# DashHub.net
KiCad netlist of a schematic drawn in EAGLE
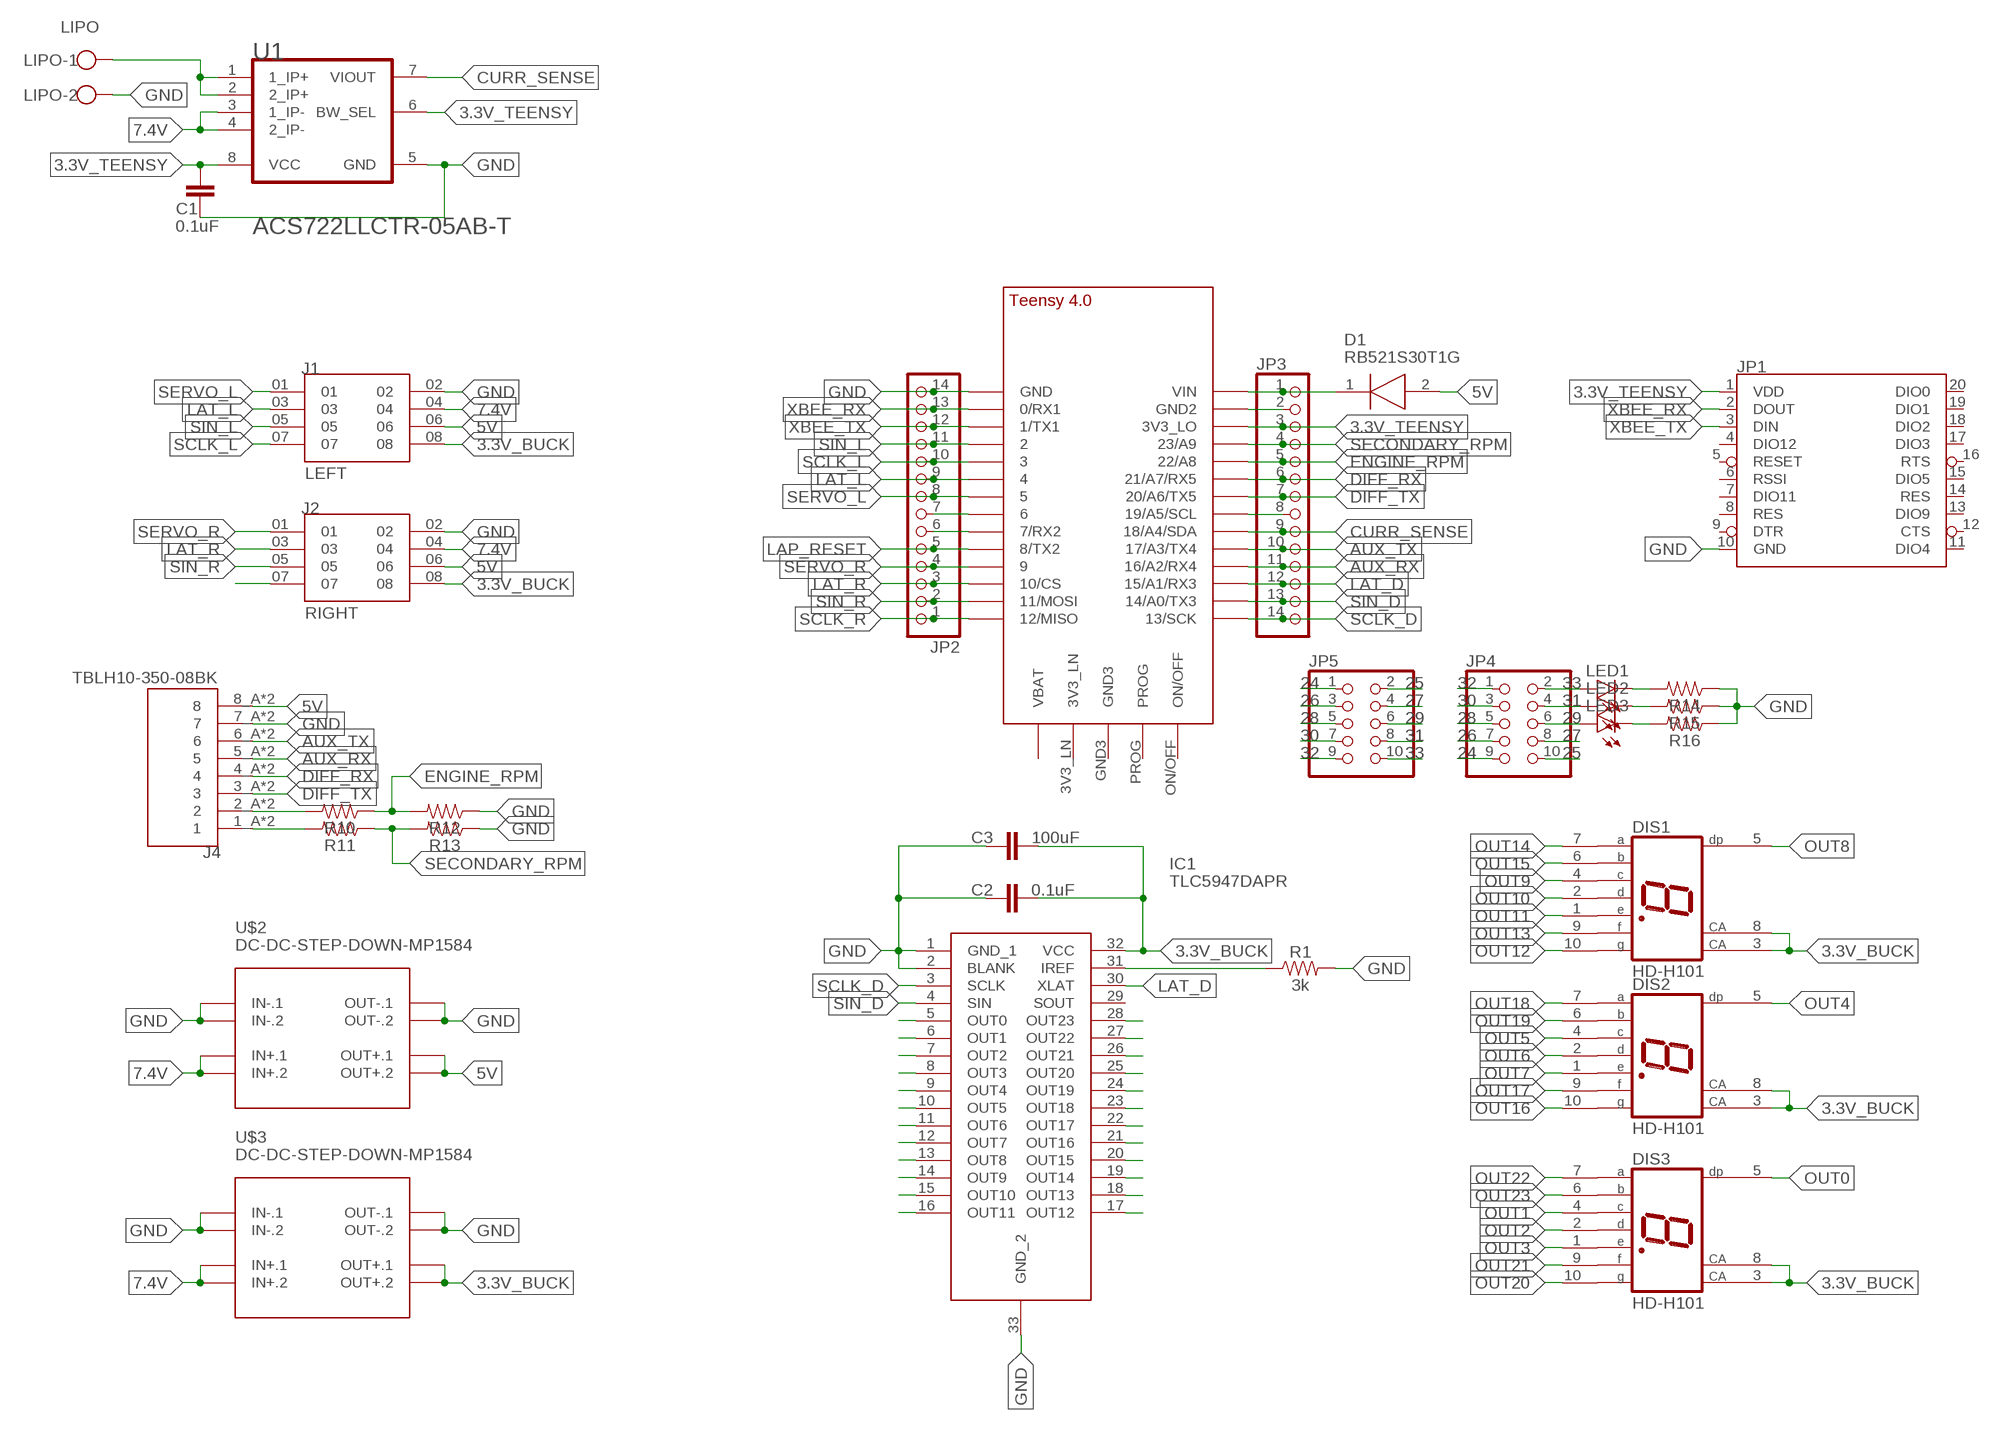
[diagram p0: schematic, sheet 1]

(export (version "E")
  (design (tool "Eeschema 10.0.6"))
  (components
    (comp (ref "C1")
      (value "0.1uF")
      (footprint "eagle-import:C0402")
      (libsource (lib "eagle-import") (part "C-EUC0402"))
    )
    (comp (ref "C2")
      (value "0.1uF")
      (footprint "eagle-import:C0402")
      (libsource (lib "eagle-import") (part "C-EUC0402"))
    )
    (comp (ref "C3")
      (value "100uF")
      (footprint "eagle-import:C1206")
      (libsource (lib "eagle-import") (part "C-EUC1206"))
    )
    (comp (ref "D1")
      (value "RB521S30T1G")
      (footprint "eagle-import:SODFL1608X70N")
      (fields (field (name "MOUSER_PART_NUMBER") "863-RB521S30T1G"))
      (libsource (lib "eagle-import") (part "RB521S30T1G"))
    )
    (comp (ref "DIS1")
      (value "HD-H101")
      (footprint "eagle-import:HDSP-M")
      (libsource (lib "eagle-import") (part "HD-H101"))
    )
    (comp (ref "DIS2")
      (value "HD-H101")
      (footprint "eagle-import:HDSP-M")
      (libsource (lib "eagle-import") (part "HD-H101"))
    )
    (comp (ref "DIS3")
      (value "HD-H101")
      (footprint "eagle-import:HDSP-M")
      (libsource (lib "eagle-import") (part "HD-H101"))
    )
    (comp (ref "IC1")
      (value "TLC5947DAPR")
      (footprint "eagle-import:SOP65P810X120-33N")
      (fields (field (name "MOUSER_PART_NUMBER") "595-TLC5947DAPR"))
      (libsource (lib "eagle-import") (part "TLC5947DAPR"))
    )
    (comp (ref "J1")
      (value "LEFT")
      (footprint "eagle-import:SAMTEC_ESW-104-23-L-D")
      (fields (field (name "MANUFACTURER") "Samtec Inc."))
      (libsource (lib "eagle-import") (part "ESW-104-23-L-D"))
    )
    (comp (ref "J2")
      (value "RIGHT")
      (footprint "eagle-import:SAMTEC_ESW-104-23-L-D")
      (fields (field (name "MANUFACTURER") "Samtec Inc."))
      (libsource (lib "eagle-import") (part "ESW-104-23-L-D"))
    )
    (comp (ref "J4")
      (value "TBLH10-350-08BK")
      (footprint "eagle-import:CUI_TBLH10-350-08BK")
      (fields (field (name "MANUFACTURER") "CUI"))
      (libsource (lib "eagle-import") (part "TBLH10-350-08BK"))
    )
    (comp (ref "JP1")
      (value "XBEE")
      (footprint "eagle-import:XBEE")
      (libsource (lib "eagle-import") (part "XBEE"))
    )
    (comp (ref "JP2")
      (value "PINHD-1X14")
      (footprint "eagle-import:1X14")
      (libsource (lib "eagle-import") (part "PINHD-1X14"))
    )
    (comp (ref "JP3")
      (value "PINHD-1X14")
      (footprint "eagle-import:1X14")
      (libsource (lib "eagle-import") (part "PINHD-1X14"))
    )
    (comp (ref "JP4")
      (value "PINHD-2X5")
      (footprint "eagle-import:2X05")
      (libsource (lib "eagle-import") (part "PINHD-2X5"))
    )
    (comp (ref "JP5")
      (value "PINHD-2X5")
      (footprint "eagle-import:2X05")
      (libsource (lib "eagle-import") (part "PINHD-2X5"))
    )
    (comp (ref "LED1")
      (value "LEDCHIPLED_1206")
      (footprint "eagle-import:CHIPLED_1206")
      (libsource (lib "eagle-import") (part "LEDCHIPLED_1206"))
    )
    (comp (ref "LED2")
      (value "LEDCHIPLED_1206")
      (footprint "eagle-import:CHIPLED_1206")
      (libsource (lib "eagle-import") (part "LEDCHIPLED_1206"))
    )
    (comp (ref "LED3")
      (value "LEDCHIPLED_1206")
      (footprint "eagle-import:CHIPLED_1206")
      (libsource (lib "eagle-import") (part "LEDCHIPLED_1206"))
    )
    (comp (ref "LIPO")
      (value "LIPO")
      (footprint "eagle-import:W237-102")
      (fields (field (name "MPN") "237-102"))
      (libsource (lib "eagle-import") (part "W237-102"))
    )
    (comp (ref "R1")
      (value "3k")
      (footprint "eagle-import:AXIAL-0.3")
      (libsource (lib "eagle-import") (part "RESISTORAXIAL-0.3"))
    )
    (comp (ref "R10")
      (value "RESISTORAXIAL-0.3")
      (footprint "eagle-import:AXIAL-0.3")
      (libsource (lib "eagle-import") (part "RESISTORAXIAL-0.3"))
    )
    (comp (ref "R11")
      (value "RESISTORAXIAL-0.3")
      (footprint "eagle-import:AXIAL-0.3")
      (libsource (lib "eagle-import") (part "RESISTORAXIAL-0.3"))
    )
    (comp (ref "R12")
      (value "RESISTORAXIAL-0.3")
      (footprint "eagle-import:AXIAL-0.3")
      (libsource (lib "eagle-import") (part "RESISTORAXIAL-0.3"))
    )
    (comp (ref "R13")
      (value "RESISTORAXIAL-0.3")
      (footprint "eagle-import:AXIAL-0.3")
      (libsource (lib "eagle-import") (part "RESISTORAXIAL-0.3"))
    )
    (comp (ref "R14")
      (value "RESISTORAXIAL-0.3")
      (footprint "eagle-import:AXIAL-0.3")
      (libsource (lib "eagle-import") (part "RESISTORAXIAL-0.3"))
    )
    (comp (ref "R15")
      (value "RESISTORAXIAL-0.3")
      (footprint "eagle-import:AXIAL-0.3")
      (libsource (lib "eagle-import") (part "RESISTORAXIAL-0.3"))
    )
    (comp (ref "R16")
      (value "RESISTORAXIAL-0.3")
      (footprint "eagle-import:AXIAL-0.3")
      (libsource (lib "eagle-import") (part "RESISTORAXIAL-0.3"))
    )
    (comp (ref "U$1")
      (value "TEENSY_4.0-BASIC")
      (footprint "eagle-import:TEENSY_4.0-BASIC")
      (libsource (lib "eagle-import") (part "TEENSY_4.0-BASIC"))
    )
    (comp (ref "U$2")
      (value "DC-DC-STEP-DOWN-MP1584")
      (footprint "eagle-import:DC-DC-STEP-DOWN-MP1584")
      (libsource (lib "eagle-import") (part "DC-DC-STEP-DOWN-MP1584"))
    )
    (comp (ref "U$3")
      (value "DC-DC-STEP-DOWN-MP1584")
      (footprint "eagle-import:DC-DC-STEP-DOWN-MP1584")
      (libsource (lib "eagle-import") (part "DC-DC-STEP-DOWN-MP1584"))
    )
    (comp (ref "U1")
      (value "ALLEGRO_MICROSYSTEMS_ACS722LLCTR-05AB-TALLEGRO_MICROSYSTEMS_ACS722LLCTR-05AB-T_0_0")
      (footprint "eagle-import:ALLEGRO_MICROSYSTEMS_ACS722LLCTR-05AB-T_0")
      (fields (field (name "MF") "Allegro MicroSystems") (field (name "MPN") "ACS722LLCTR-05AB-T"))
      (libsource (lib "eagle-import") (part "ALLEGRO_MICROSYSTEMS_ACS722LLCTR-05AB-TALLEGRO_MICROSYSTEMS_ACS722LLCTR-05AB-T_0_0"))
    )
  )
  (nets
    (net (code "1") (name "/24") (class "Default")
      (node (ref "JP4") (pin "9") (pinfunction "9_9") (pintype "passive"))
      (node (ref "JP5") (pin "1") (pinfunction "1_1") (pintype "passive"))
    )
    (net (code "2") (name "/25") (class "Default")
      (node (ref "JP4") (pin "10") (pinfunction "10_10") (pintype "passive"))
      (node (ref "JP5") (pin "2") (pinfunction "2_2") (pintype "passive"))
    )
    (net (code "3") (name "/26") (class "Default")
      (node (ref "JP4") (pin "7") (pinfunction "7_7") (pintype "passive"))
      (node (ref "JP5") (pin "3") (pinfunction "3_3") (pintype "passive"))
    )
    (net (code "4") (name "/27") (class "Default")
      (node (ref "JP4") (pin "8") (pinfunction "8_8") (pintype "passive"))
      (node (ref "JP5") (pin "4") (pinfunction "4_4") (pintype "passive"))
    )
    (net (code "5") (name "/28") (class "Default")
      (node (ref "JP4") (pin "5") (pinfunction "5_5") (pintype "passive"))
      (node (ref "JP5") (pin "5") (pinfunction "5_5") (pintype "passive"))
    )
    (net (code "6") (name "/29") (class "Default")
      (node (ref "JP4") (pin "6") (pinfunction "6_6") (pintype "passive"))
      (node (ref "JP5") (pin "6") (pinfunction "6_6") (pintype "passive"))
      (node (ref "LED3") (pin "A") (pinfunction "A_A") (pintype "passive"))
    )
    (net (code "7") (name "/30") (class "Default")
      (node (ref "JP4") (pin "3") (pinfunction "3_3") (pintype "passive"))
      (node (ref "JP5") (pin "7") (pinfunction "7_7") (pintype "passive"))
    )
    (net (code "8") (name "/31") (class "Default")
      (node (ref "JP4") (pin "4") (pinfunction "4_4") (pintype "passive"))
      (node (ref "JP5") (pin "8") (pinfunction "8_8") (pintype "passive"))
      (node (ref "LED2") (pin "A") (pinfunction "A_A") (pintype "passive"))
    )
    (net (code "9") (name "/32") (class "Default")
      (node (ref "JP4") (pin "1") (pinfunction "1_1") (pintype "passive"))
      (node (ref "JP5") (pin "9") (pinfunction "9_9") (pintype "passive"))
    )
    (net (code "10") (name "/33") (class "Default")
      (node (ref "JP4") (pin "2") (pinfunction "2_2") (pintype "passive"))
      (node (ref "JP5") (pin "10") (pinfunction "10_10") (pintype "passive"))
      (node (ref "LED1") (pin "A") (pinfunction "A_A") (pintype "passive"))
    )
    (net (code "11") (name "3.3V_BUCK") (class "Default")
      (node (ref "C2") (pin "2") (pinfunction "2_2") (pintype "passive"))
      (node (ref "C3") (pin "2") (pinfunction "2_2") (pintype "passive"))
      (node (ref "DIS1") (pin "3") (pinfunction "CA_3") (pintype "passive"))
      (node (ref "DIS1") (pin "8") (pinfunction "CA_8") (pintype "passive"))
      (node (ref "DIS2") (pin "3") (pinfunction "CA_3") (pintype "passive"))
      (node (ref "DIS2") (pin "8") (pinfunction "CA_8") (pintype "passive"))
      (node (ref "DIS3") (pin "3") (pinfunction "CA_3") (pintype "passive"))
      (node (ref "DIS3") (pin "8") (pinfunction "CA_8") (pintype "passive"))
      (node (ref "IC1") (pin "32") (pinfunction "VCC_32") (pintype "power_in"))
      (node (ref "J1") (pin "08") (pinfunction "08_08") (pintype "passive"))
      (node (ref "J2") (pin "08") (pinfunction "08_08") (pintype "passive"))
      (node (ref "U$3") (pin "OUT+.1") (pinfunction "OUT+.1_OUT+.1") (pintype "bidirectional"))
      (node (ref "U$3") (pin "OUT+.2") (pinfunction "OUT+.2_OUT+.2") (pintype "bidirectional"))
    )
    (net (code "12") (name "3.3V_TEENSY") (class "Default")
      (node (ref "C1") (pin "2") (pinfunction "2_2") (pintype "passive"))
      (node (ref "JP1") (pin "1") (pinfunction "VDD_1") (pintype "power_in"))
      (node (ref "JP3") (pin "3") (pinfunction "3_3") (pintype "passive"))
      (node (ref "U$1") (pin "3V3_LO") (pinfunction "3V3_LO_3V3_LO") (pintype "bidirectional"))
      (node (ref "U1") (pin "6") (pinfunction "BW_SEL_6") (pintype "input"))
      (node (ref "U1") (pin "8") (pinfunction "VCC_8") (pintype "power_in"))
    )
    (net (code "13") (name "5V") (class "Default")
      (node (ref "D1") (pin "2") (pinfunction "A_2") (pintype "bidirectional"))
      (node (ref "J1") (pin "06") (pinfunction "06_06") (pintype "passive"))
      (node (ref "J2") (pin "06") (pinfunction "06_06") (pintype "passive"))
      (node (ref "J4") (pin "8_A") (pinfunction "8_8_A") (pintype "passive"))
      (node (ref "J4") (pin "8_B") (pinfunction "8_8_B") (pintype "passive"))
      (node (ref "U$2") (pin "OUT+.1") (pinfunction "OUT+.1_OUT+.1") (pintype "bidirectional"))
      (node (ref "U$2") (pin "OUT+.2") (pinfunction "OUT+.2_OUT+.2") (pintype "bidirectional"))
    )
    (net (code "14") (name "7.4V") (class "Default")
      (node (ref "J1") (pin "04") (pinfunction "04_04") (pintype "passive"))
      (node (ref "J2") (pin "04") (pinfunction "04_04") (pintype "passive"))
      (node (ref "U$2") (pin "IN+.1") (pinfunction "IN+.1_IN+.1") (pintype "bidirectional"))
      (node (ref "U$2") (pin "IN+.2") (pinfunction "IN+.2_IN+.2") (pintype "bidirectional"))
      (node (ref "U$3") (pin "IN+.1") (pinfunction "IN+.1_IN+.1") (pintype "bidirectional"))
      (node (ref "U$3") (pin "IN+.2") (pinfunction "IN+.2_IN+.2") (pintype "bidirectional"))
      (node (ref "U1") (pin "3") (pinfunction "1_IP-_3") (pintype "input"))
      (node (ref "U1") (pin "4") (pinfunction "2_IP-_4") (pintype "input"))
    )
    (net (code "15") (name "AUX_RX") (class "Default")
      (node (ref "J4") (pin "5_A") (pinfunction "5_5_A") (pintype "passive"))
      (node (ref "J4") (pin "5_B") (pinfunction "5_5_B") (pintype "passive"))
      (node (ref "JP3") (pin "11") (pinfunction "11_11") (pintype "passive"))
      (node (ref "U$1") (pin "16/A2") (pinfunction "16/A2/RX4_16/A2") (pintype "bidirectional"))
    )
    (net (code "16") (name "AUX_TX") (class "Default")
      (node (ref "J4") (pin "6_A") (pinfunction "6_6_A") (pintype "passive"))
      (node (ref "J4") (pin "6_B") (pinfunction "6_6_B") (pintype "passive"))
      (node (ref "JP3") (pin "10") (pinfunction "10_10") (pintype "passive"))
      (node (ref "U$1") (pin "17/A3") (pinfunction "17/A3/TX4_17/A3") (pintype "bidirectional"))
    )
    (net (code "17") (name "CURR_SENSE") (class "Default")
      (node (ref "JP3") (pin "9") (pinfunction "9_9") (pintype "passive"))
      (node (ref "U$1") (pin "18/A4/SDA") (pinfunction "18/A4/SDA_18/A4/SDA") (pintype "bidirectional"))
      (node (ref "U1") (pin "7") (pinfunction "VIOUT_7") (pintype "output"))
    )
    (net (code "18") (name "DIFF_RX") (class "Default")
      (node (ref "J4") (pin "4_A") (pinfunction "4_4_A") (pintype "passive"))
      (node (ref "J4") (pin "4_B") (pinfunction "4_4_B") (pintype "passive"))
      (node (ref "JP3") (pin "6") (pinfunction "6_6") (pintype "passive"))
      (node (ref "U$1") (pin "21/A7") (pinfunction "21/A7/RX5_21/A7") (pintype "bidirectional"))
    )
    (net (code "19") (name "DIFF_TX") (class "Default")
      (node (ref "J4") (pin "3_A") (pinfunction "3_3_A") (pintype "passive"))
      (node (ref "J4") (pin "3_B") (pinfunction "3_3_B") (pintype "passive"))
      (node (ref "JP3") (pin "7") (pinfunction "7_7") (pintype "passive"))
      (node (ref "U$1") (pin "20/A6") (pinfunction "20/A6/TX5_20/A6") (pintype "bidirectional"))
    )
    (net (code "20") (name "ENGINE_RPM") (class "Default")
      (node (ref "JP3") (pin "5") (pinfunction "5_5") (pintype "passive"))
      (node (ref "R10") (pin "P$1") (pinfunction "1_P$1") (pintype "passive"))
      (node (ref "R12") (pin "P$2") (pinfunction "2_P$2") (pintype "passive"))
      (node (ref "U$1") (pin "22/A8") (pinfunction "22/A8_22/A8") (pintype "bidirectional"))
    )
    (net (code "21") (name "GND") (class "Default")
      (node (ref "C1") (pin "1") (pinfunction "1_1") (pintype "passive"))
      (node (ref "C2") (pin "1") (pinfunction "1_1") (pintype "passive"))
      (node (ref "C3") (pin "1") (pinfunction "1_1") (pintype "passive"))
      (node (ref "IC1") (pin "1") (pinfunction "GND_1_1") (pintype "power_in"))
      (node (ref "IC1") (pin "2") (pinfunction "BLANK_2") (pintype "input"))
      (node (ref "IC1") (pin "33") (pinfunction "GND_2_33") (pintype "power_in"))
      (node (ref "J1") (pin "02") (pinfunction "02_02") (pintype "passive"))
      (node (ref "J2") (pin "02") (pinfunction "02_02") (pintype "passive"))
      (node (ref "J4") (pin "7_A") (pinfunction "7_7_A") (pintype "passive"))
      (node (ref "J4") (pin "7_B") (pinfunction "7_7_B") (pintype "passive"))
      (node (ref "JP1") (pin "10") (pinfunction "GND_10") (pintype "power_in"))
      (node (ref "JP2") (pin "14") (pinfunction "14_14") (pintype "passive"))
      (node (ref "LIPO") (pin "2") (pinfunction "KL_2") (pintype "passive"))
      (node (ref "R1") (pin "P$2") (pinfunction "2_P$2") (pintype "passive"))
      (node (ref "R12") (pin "P$1") (pinfunction "1_P$1") (pintype "passive"))
      (node (ref "R13") (pin "P$1") (pinfunction "1_P$1") (pintype "passive"))
      (node (ref "R14") (pin "P$1") (pinfunction "1_P$1") (pintype "passive"))
      (node (ref "R15") (pin "P$1") (pinfunction "1_P$1") (pintype "passive"))
      (node (ref "R16") (pin "P$1") (pinfunction "1_P$1") (pintype "passive"))
      (node (ref "U$1") (pin "GND") (pinfunction "GND_GND") (pintype "bidirectional"))
      (node (ref "U$2") (pin "IN-.1") (pinfunction "IN-.1_IN-.1") (pintype "bidirectional"))
      (node (ref "U$2") (pin "IN-.2") (pinfunction "IN-.2_IN-.2") (pintype "bidirectional"))
      (node (ref "U$2") (pin "OUT-.1") (pinfunction "OUT-.1_OUT-.1") (pintype "bidirectional"))
      (node (ref "U$2") (pin "OUT-.2") (pinfunction "OUT-.2_OUT-.2") (pintype "bidirectional"))
      (node (ref "U$3") (pin "IN-.1") (pinfunction "IN-.1_IN-.1") (pintype "bidirectional"))
      (node (ref "U$3") (pin "IN-.2") (pinfunction "IN-.2_IN-.2") (pintype "bidirectional"))
      (node (ref "U$3") (pin "OUT-.1") (pinfunction "OUT-.1_OUT-.1") (pintype "bidirectional"))
      (node (ref "U$3") (pin "OUT-.2") (pinfunction "OUT-.2_OUT-.2") (pintype "bidirectional"))
      (node (ref "U1") (pin "5") (pinfunction "GND_5") (pintype "power_in"))
    )
    (net (code "22") (name "LAP_RESET") (class "Default")
      (node (ref "JP2") (pin "5") (pinfunction "5_5") (pintype "passive"))
      (node (ref "U$1") (pin "8") (pinfunction "8/TX2_8") (pintype "bidirectional"))
    )
    (net (code "23") (name "LAT_D") (class "Default")
      (node (ref "IC1") (pin "30") (pinfunction "XLAT_30") (pintype "input"))
      (node (ref "JP3") (pin "12") (pinfunction "12_12") (pintype "passive"))
      (node (ref "U$1") (pin "15/A1") (pinfunction "15/A1/RX3_15/A1") (pintype "bidirectional"))
    )
    (net (code "24") (name "LAT_L") (class "Default")
      (node (ref "J1") (pin "03") (pinfunction "03_03") (pintype "passive"))
      (node (ref "JP2") (pin "9") (pinfunction "9_9") (pintype "passive"))
      (node (ref "U$1") (pin "4/CANRX") (pinfunction "4_4/CANRX") (pintype "bidirectional"))
    )
    (net (code "25") (name "LAT_R") (class "Default")
      (node (ref "J2") (pin "03") (pinfunction "03_03") (pintype "passive"))
      (node (ref "JP2") (pin "3") (pinfunction "3_3") (pintype "passive"))
      (node (ref "U$1") (pin "10/CS") (pinfunction "10/CS_10/CS") (pintype "bidirectional"))
    )
    (net (code "26") (name "Net-(D1-K)") (class "Default")
      (node (ref "D1") (pin "1") (pinfunction "K_1") (pintype "bidirectional"))
      (node (ref "JP3") (pin "1") (pinfunction "1_1") (pintype "passive"))
      (node (ref "U$1") (pin "VIN") (pinfunction "VIN_VIN") (pintype "bidirectional"))
    )
    (net (code "27") (name "Net-(IC1-IREF)") (class "Default")
      (node (ref "IC1") (pin "31") (pinfunction "IREF_31") (pintype "input"))
      (node (ref "R1") (pin "P$1") (pinfunction "1_P$1") (pintype "passive"))
    )
    (net (code "28") (name "Net-(JP2-Pad7)") (class "Default")
      (node (ref "JP2") (pin "7") (pinfunction "7_7") (pintype "passive"))
      (node (ref "U$1") (pin "6") (pinfunction "6_6") (pintype "bidirectional"))
    )
    (net (code "29") (name "Net-(JP3-Pad2)") (class "Default")
      (node (ref "JP3") (pin "2") (pinfunction "2_2") (pintype "passive"))
      (node (ref "U$1") (pin "GND2") (pinfunction "GND2_GND2") (pintype "bidirectional"))
    )
    (net (code "30") (name "Net-(JP3-Pad8)") (class "Default")
      (node (ref "JP3") (pin "8") (pinfunction "8_8") (pintype "passive"))
      (node (ref "U$1") (pin "19/A5/SCL") (pinfunction "19/A5/SCL_19/A5/SCL") (pintype "bidirectional"))
    )
    (net (code "31") (name "Net-(LIPOA-KL)") (class "Default")
      (node (ref "LIPO") (pin "1") (pinfunction "KL_1") (pintype "passive"))
      (node (ref "U1") (pin "1") (pinfunction "1_IP+_1") (pintype "input"))
      (node (ref "U1") (pin "2") (pinfunction "2_IP+_2") (pintype "input"))
    )
    (net (code "32") (name "Net-(R10-2)") (class "Default")
      (node (ref "J4") (pin "2_A") (pinfunction "2_2_A") (pintype "passive"))
      (node (ref "J4") (pin "2_B") (pinfunction "2_2_B") (pintype "passive"))
      (node (ref "R10") (pin "P$2") (pinfunction "2_P$2") (pintype "passive"))
    )
    (net (code "33") (name "Net-(R11-2)") (class "Default")
      (node (ref "J4") (pin "1_A") (pinfunction "1_1_A") (pintype "passive"))
      (node (ref "J4") (pin "1_B") (pinfunction "1_1_B") (pintype "passive"))
      (node (ref "R11") (pin "P$2") (pinfunction "2_P$2") (pintype "passive"))
    )
    (net (code "34") (name "Net-(R14-2)") (class "Default")
      (node (ref "LED1") (pin "C") (pinfunction "C_C") (pintype "passive"))
      (node (ref "R14") (pin "P$2") (pinfunction "2_P$2") (pintype "passive"))
    )
    (net (code "35") (name "Net-(R15-2)") (class "Default")
      (node (ref "LED2") (pin "C") (pinfunction "C_C") (pintype "passive"))
      (node (ref "R15") (pin "P$2") (pinfunction "2_P$2") (pintype "passive"))
    )
    (net (code "36") (name "Net-(R16-2)") (class "Default")
      (node (ref "LED3") (pin "C") (pinfunction "C_C") (pintype "passive"))
      (node (ref "R16") (pin "P$2") (pinfunction "2_P$2") (pintype "passive"))
    )
    (net (code "37") (name "Net-(U$1-7{slash}RX2)") (class "Default")
      (node (ref "JP2") (pin "6") (pinfunction "6_6") (pintype "passive"))
      (node (ref "U$1") (pin "7") (pinfunction "7/RX2_7") (pintype "bidirectional"))
    )
    (net (code "38") (name "OUT0") (class "Default")
      (node (ref "DIS3") (pin "5") (pinfunction "DP_5") (pintype "passive"))
      (node (ref "IC1") (pin "5") (pinfunction "OUT0_5") (pintype "output"))
    )
    (net (code "39") (name "OUT1") (class "Default")
      (node (ref "DIS3") (pin "4") (pinfunction "C_4") (pintype "passive"))
      (node (ref "IC1") (pin "6") (pinfunction "OUT1_6") (pintype "output"))
    )
    (net (code "40") (name "OUT2") (class "Default")
      (node (ref "DIS3") (pin "2") (pinfunction "D_2") (pintype "passive"))
      (node (ref "IC1") (pin "7") (pinfunction "OUT2_7") (pintype "output"))
    )
    (net (code "41") (name "OUT3") (class "Default")
      (node (ref "DIS3") (pin "1") (pinfunction "E_1") (pintype "passive"))
      (node (ref "IC1") (pin "8") (pinfunction "OUT3_8") (pintype "output"))
    )
    (net (code "42") (name "OUT4") (class "Default")
      (node (ref "DIS2") (pin "5") (pinfunction "DP_5") (pintype "passive"))
      (node (ref "IC1") (pin "9") (pinfunction "OUT4_9") (pintype "output"))
    )
    (net (code "43") (name "OUT5") (class "Default")
      (node (ref "DIS2") (pin "4") (pinfunction "C_4") (pintype "passive"))
      (node (ref "IC1") (pin "10") (pinfunction "OUT5_10") (pintype "output"))
    )
    (net (code "44") (name "OUT6") (class "Default")
      (node (ref "DIS2") (pin "2") (pinfunction "D_2") (pintype "passive"))
      (node (ref "IC1") (pin "11") (pinfunction "OUT6_11") (pintype "output"))
    )
    (net (code "45") (name "OUT7") (class "Default")
      (node (ref "DIS2") (pin "1") (pinfunction "E_1") (pintype "passive"))
      (node (ref "IC1") (pin "12") (pinfunction "OUT7_12") (pintype "output"))
    )
    (net (code "46") (name "OUT8") (class "Default")
      (node (ref "DIS1") (pin "5") (pinfunction "DP_5") (pintype "passive"))
      (node (ref "IC1") (pin "13") (pinfunction "OUT8_13") (pintype "output"))
    )
    (net (code "47") (name "OUT9") (class "Default")
      (node (ref "DIS1") (pin "4") (pinfunction "C_4") (pintype "passive"))
      (node (ref "IC1") (pin "14") (pinfunction "OUT9_14") (pintype "output"))
    )
    (net (code "48") (name "OUT10") (class "Default")
      (node (ref "DIS1") (pin "2") (pinfunction "D_2") (pintype "passive"))
      (node (ref "IC1") (pin "15") (pinfunction "OUT10_15") (pintype "output"))
    )
    (net (code "49") (name "OUT11") (class "Default")
      (node (ref "DIS1") (pin "1") (pinfunction "E_1") (pintype "passive"))
      (node (ref "IC1") (pin "16") (pinfunction "OUT11_16") (pintype "output"))
    )
    (net (code "50") (name "OUT12") (class "Default")
      (node (ref "DIS1") (pin "10") (pinfunction "G_10") (pintype "passive"))
      (node (ref "IC1") (pin "17") (pinfunction "OUT12_17") (pintype "output"))
    )
    (net (code "51") (name "OUT13") (class "Default")
      (node (ref "DIS1") (pin "9") (pinfunction "F_9") (pintype "passive"))
      (node (ref "IC1") (pin "18") (pinfunction "OUT13_18") (pintype "output"))
    )
    (net (code "52") (name "OUT14") (class "Default")
      (node (ref "DIS1") (pin "7") (pinfunction "A_7") (pintype "passive"))
      (node (ref "IC1") (pin "19") (pinfunction "OUT14_19") (pintype "output"))
    )
    (net (code "53") (name "OUT15") (class "Default")
      (node (ref "DIS1") (pin "6") (pinfunction "B_6") (pintype "passive"))
      (node (ref "IC1") (pin "20") (pinfunction "OUT15_20") (pintype "output"))
    )
    (net (code "54") (name "OUT16") (class "Default")
      (node (ref "DIS2") (pin "10") (pinfunction "G_10") (pintype "passive"))
      (node (ref "IC1") (pin "21") (pinfunction "OUT16_21") (pintype "output"))
    )
    (net (code "55") (name "OUT17") (class "Default")
      (node (ref "DIS2") (pin "9") (pinfunction "F_9") (pintype "passive"))
      (node (ref "IC1") (pin "22") (pinfunction "OUT17_22") (pintype "output"))
    )
    (net (code "56") (name "OUT18") (class "Default")
      (node (ref "DIS2") (pin "7") (pinfunction "A_7") (pintype "passive"))
      (node (ref "IC1") (pin "23") (pinfunction "OUT18_23") (pintype "output"))
    )
    (net (code "57") (name "OUT19") (class "Default")
      (node (ref "DIS2") (pin "6") (pinfunction "B_6") (pintype "passive"))
      (node (ref "IC1") (pin "24") (pinfunction "OUT19_24") (pintype "output"))
    )
    (net (code "58") (name "OUT20") (class "Default")
      (node (ref "DIS3") (pin "10") (pinfunction "G_10") (pintype "passive"))
      (node (ref "IC1") (pin "25") (pinfunction "OUT20_25") (pintype "output"))
    )
    (net (code "59") (name "OUT21") (class "Default")
      (node (ref "DIS3") (pin "9") (pinfunction "F_9") (pintype "passive"))
      (node (ref "IC1") (pin "26") (pinfunction "OUT21_26") (pintype "output"))
    )
    (net (code "60") (name "OUT22") (class "Default")
      (node (ref "DIS3") (pin "7") (pinfunction "A_7") (pintype "passive"))
      (node (ref "IC1") (pin "27") (pinfunction "OUT22_27") (pintype "output"))
    )
    (net (code "61") (name "OUT23") (class "Default")
      (node (ref "DIS3") (pin "6") (pinfunction "B_6") (pintype "passive"))
      (node (ref "IC1") (pin "28") (pinfunction "OUT23_28") (pintype "output"))
    )
    (net (code "62") (name "SCLK_D") (class "Default")
      (node (ref "IC1") (pin "3") (pinfunction "SCLK_3") (pintype "input"))
      (node (ref "JP3") (pin "14") (pinfunction "14_14") (pintype "passive"))
      (node (ref "U$1") (pin "13/SCK") (pinfunction "13/SCK_13/SCK") (pintype "bidirectional"))
    )
    (net (code "63") (name "SCLK_L") (class "Default")
      (node (ref "J1") (pin "07") (pinfunction "07_07") (pintype "passive"))
      (node (ref "JP2") (pin "10") (pinfunction "10_10") (pintype "passive"))
      (node (ref "U$1") (pin "3/CANTX") (pinfunction "3_3/CANTX") (pintype "bidirectional"))
    )
    (net (code "64") (name "SCLK_R") (class "Default")
      (node (ref "J2") (pin "07") (pinfunction "07_07") (pintype "passive"))
      (node (ref "JP2") (pin "1") (pinfunction "1_1") (pintype "passive"))
      (node (ref "U$1") (pin "12/MISO") (pinfunction "12/MISO_12/MISO") (pintype "bidirectional"))
    )
    (net (code "65") (name "SECONDARY_RPM") (class "Default")
      (node (ref "JP3") (pin "4") (pinfunction "4_4") (pintype "passive"))
      (node (ref "R11") (pin "P$1") (pinfunction "1_P$1") (pintype "passive"))
      (node (ref "R13") (pin "P$2") (pinfunction "2_P$2") (pintype "passive"))
      (node (ref "U$1") (pin "23/A9") (pinfunction "23/A9_23/A9") (pintype "bidirectional"))
    )
    (net (code "66") (name "SERVO_L") (class "Default")
      (node (ref "J1") (pin "01") (pinfunction "01_01") (pintype "passive"))
      (node (ref "JP2") (pin "8") (pinfunction "8_8") (pintype "passive"))
      (node (ref "U$1") (pin "5") (pinfunction "5_5") (pintype "bidirectional"))
    )
    (net (code "67") (name "SERVO_R") (class "Default")
      (node (ref "J2") (pin "01") (pinfunction "01_01") (pintype "passive"))
      (node (ref "JP2") (pin "4") (pinfunction "4_4") (pintype "passive"))
      (node (ref "U$1") (pin "9/CS") (pinfunction "9_9/CS") (pintype "bidirectional"))
    )
    (net (code "68") (name "SIN_D") (class "Default")
      (node (ref "IC1") (pin "4") (pinfunction "SIN_4") (pintype "input"))
      (node (ref "JP3") (pin "13") (pinfunction "13_13") (pintype "passive"))
      (node (ref "U$1") (pin "14/A0") (pinfunction "14/A0/TX3_14/A0") (pintype "bidirectional"))
    )
    (net (code "69") (name "SIN_L") (class "Default")
      (node (ref "J1") (pin "05") (pinfunction "05_05") (pintype "passive"))
      (node (ref "JP2") (pin "11") (pinfunction "11_11") (pintype "passive"))
      (node (ref "U$1") (pin "2") (pinfunction "2_2") (pintype "bidirectional"))
    )
    (net (code "70") (name "SIN_R") (class "Default")
      (node (ref "J2") (pin "05") (pinfunction "05_05") (pintype "passive"))
      (node (ref "JP2") (pin "2") (pinfunction "2_2") (pintype "passive"))
      (node (ref "U$1") (pin "11/MOSI") (pinfunction "11/MOSI_11/MOSI") (pintype "bidirectional"))
    )
    (net (code "71") (name "XBEE_RX") (class "Default")
      (node (ref "JP1") (pin "2") (pinfunction "DOUT_2") (pintype "output"))
      (node (ref "JP2") (pin "13") (pinfunction "13_13") (pintype "passive"))
      (node (ref "U$1") (pin "0/RX") (pinfunction "0/RX1_0/RX") (pintype "bidirectional"))
    )
    (net (code "72") (name "XBEE_TX") (class "Default")
      (node (ref "JP1") (pin "3") (pinfunction "DIN_3") (pintype "input"))
      (node (ref "JP2") (pin "12") (pinfunction "12_12") (pintype "passive"))
      (node (ref "U$1") (pin "1/TX") (pinfunction "1/TX1_1/TX") (pintype "bidirectional"))
    )
    (net (code "73") (name "unconnected-(IC1-SOUT-Pad29)") (class "Default")
      (node (ref "IC1") (pin "29") (pinfunction "SOUT_29") (pintype "output"))
    )
    (net (code "74") (name "unconnected-(JP1-CTS-Pad12)") (class "Default")
      (node (ref "JP1") (pin "12") (pinfunction "CTS_12") (pintype "output"))
    )
    (net (code "75") (name "unconnected-(JP1-DIO0-Pad20)") (class "Default")
      (node (ref "JP1") (pin "20") (pinfunction "DIO0_20") (pintype "bidirectional"))
    )
    (net (code "76") (name "unconnected-(JP1-DIO1-Pad19)") (class "Default")
      (node (ref "JP1") (pin "19") (pinfunction "DIO1_19") (pintype "bidirectional"))
    )
    (net (code "77") (name "unconnected-(JP1-DIO2-Pad18)") (class "Default")
      (node (ref "JP1") (pin "18") (pinfunction "DIO2_18") (pintype "bidirectional"))
    )
    (net (code "78") (name "unconnected-(JP1-DIO3-Pad17)") (class "Default")
      (node (ref "JP1") (pin "17") (pinfunction "DIO3_17") (pintype "bidirectional"))
    )
    (net (code "79") (name "unconnected-(JP1-DIO4-Pad11)") (class "Default")
      (node (ref "JP1") (pin "11") (pinfunction "DIO4_11") (pintype "bidirectional"))
    )
    (net (code "80") (name "unconnected-(JP1-DIO5-Pad15)") (class "Default")
      (node (ref "JP1") (pin "15") (pinfunction "DIO5_15") (pintype "bidirectional"))
    )
    (net (code "81") (name "unconnected-(JP1-DIO9-Pad13)") (class "Default")
      (node (ref "JP1") (pin "13") (pinfunction "DIO9_13") (pintype "bidirectional"))
    )
    (net (code "82") (name "unconnected-(JP1-DIO11-Pad7)") (class "Default")
      (node (ref "JP1") (pin "7") (pinfunction "DIO11_7") (pintype "bidirectional"))
    )
    (net (code "83") (name "unconnected-(JP1-DIO12-Pad4)") (class "Default")
      (node (ref "JP1") (pin "4") (pinfunction "DIO12_4") (pintype "bidirectional"))
    )
    (net (code "84") (name "unconnected-(JP1-DTR-Pad9)") (class "Default")
      (node (ref "JP1") (pin "9") (pinfunction "DTR_9") (pintype "bidirectional"))
    )
    (net (code "85") (name "unconnected-(JP1-RES-Pad8)") (class "Default")
      (node (ref "JP1") (pin "8") (pinfunction "RES_8") (pintype "bidirectional"))
    )
    (net (code "86") (name "unconnected-(JP1-RES-Pad14)") (class "Default")
      (node (ref "JP1") (pin "14") (pinfunction "RES_14") (pintype "bidirectional"))
    )
    (net (code "87") (name "unconnected-(JP1-RESET-Pad5)") (class "Default")
      (node (ref "JP1") (pin "5") (pinfunction "RESET_5") (pintype "input"))
    )
    (net (code "88") (name "unconnected-(JP1-RSSI-Pad6)") (class "Default")
      (node (ref "JP1") (pin "6") (pinfunction "RSSI_6") (pintype "bidirectional"))
    )
    (net (code "89") (name "unconnected-(JP1-RTS-Pad16)") (class "Default")
      (node (ref "JP1") (pin "16") (pinfunction "RTS_16") (pintype "input"))
    )
    (net (code "90") (name "unconnected-(U$1-Pad3V3_LN)") (class "Default")
      (node (ref "U$1") (pin "3V3_LN") (pinfunction "3V3_LN_3V3_LN") (pintype "bidirectional"))
    )
    (net (code "91") (name "unconnected-(U$1-PadGND3)") (class "Default")
      (node (ref "U$1") (pin "GND3") (pinfunction "GND3_GND3") (pintype "bidirectional"))
    )
    (net (code "92") (name "unconnected-(U$1-PadON{slash}OFF)") (class "Default")
      (node (ref "U$1") (pin "ON/OFF") (pinfunction "ON/OFF_ON/OFF") (pintype "bidirectional"))
    )
    (net (code "93") (name "unconnected-(U$1-PadPROG)") (class "Default")
      (node (ref "U$1") (pin "PROG") (pinfunction "PROG_PROG") (pintype "bidirectional"))
    )
    (net (code "94") (name "unconnected-(U$1-VBAT-PadVBAT\\)") (class "Default")
      (node (ref "U$1") (pin "VBAT\\") (pinfunction "VBAT_VBAT\\") (pintype "bidirectional"))
    )
  )
)
